# connectors.net
KiCad netlist of a schematic drawn in Altium Designer
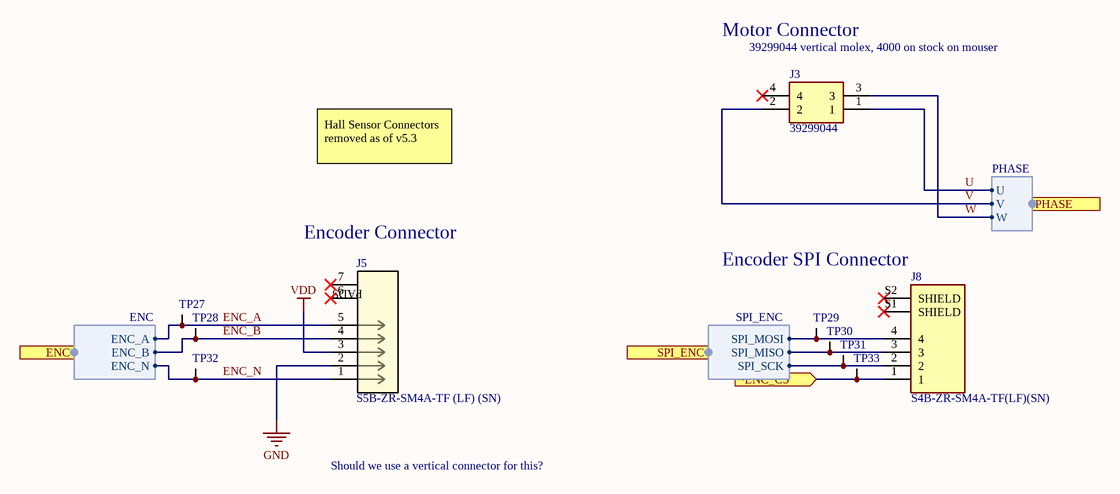
[diagram p0: connectors.SchDoc]

(export (version "E")
  (design (tool "Eeschema 10.0.6"))
  (components
    (comp (ref "J3")
      (value "39299044")
      (footprint "39299044")
      (description "Molex 39299044 4POS Minifit\r\ndual row, vertical")
      (fields (field (name "PART NUMBER") "CN HDR 4POS Molex 39299044 VERT"))
      (libsource (lib "Connector_Library") (part "CN HDR 4POS Molex 39299044 VERT"))
    )
    (comp (ref "J5")
      (value "S5B-ZR-SM4A-TF (LF) (SN)")
      (footprint "JST_S5B-ZR-SM4A-TF")
      (description "Connector Header Surface Mount, Right Angle 5 position 0.059\" (1.50mm)")
      (fields (field (name "PART NUMBER") "CN 5POS JST ZR RA"))
      (libsource (lib "Connector_Library") (part "CN 5POS JST ZR RA"))
    )
    (comp (ref "J8")
      (value "S4B-ZR-SM4A-TF(LF)(SN)")
      (footprint "JST_S4B-ZR-SM4A-TF(LF)(SN)")
      (description "Connector Header Surface Mount, Right Angle 4 position 0.059 (1.50mm)")
      (fields (field (name "MF") "JST Sales") (field (name "PART NUMBER") "CN 4POS JST ZR RA"))
      (libsource (lib "Connector_Library") (part "CN HDR 4POS SMD JST ZR"))
    )
    (comp (ref "TP27")
      (value "ENC_A")
      (footprint "TP")
      (fields (field (name "PART NUMBER") "Test Point (Via)"))
      (libsource (lib "IC_Library") (part "Test Point (Via)"))
    )
    (comp (ref "TP28")
      (value "ENC_B")
      (footprint "TP")
      (fields (field (name "PART NUMBER") "Test Point (Via)"))
      (libsource (lib "IC_Library") (part "Test Point (Via)"))
    )
    (comp (ref "TP29")
      (value "MOSI")
      (footprint "TP")
      (fields (field (name "PART NUMBER") "Test Point (Via)"))
      (libsource (lib "IC_Library") (part "Test Point (Via)"))
    )
    (comp (ref "TP30")
      (value "MISO")
      (footprint "TP")
      (fields (field (name "PART NUMBER") "Test Point (Via)"))
      (libsource (lib "IC_Library") (part "Test Point (Via)"))
    )
    (comp (ref "TP31")
      (value "SCK")
      (footprint "TP")
      (fields (field (name "PART NUMBER") "Test Point (Via)"))
      (libsource (lib "IC_Library") (part "Test Point (Via)"))
    )
    (comp (ref "TP32")
      (value "ENC_N")
      (footprint "TP")
      (fields (field (name "PART NUMBER") "Test Point (Via)"))
      (libsource (lib "IC_Library") (part "Test Point (Via)"))
    )
    (comp (ref "TP33")
      (value "ENC_CS")
      (footprint "TP")
      (fields (field (name "PART NUMBER") "Test Point (Via)"))
      (libsource (lib "IC_Library") (part "Test Point (Via)"))
    )
  )
  (nets
    (net (code "5") (name "/ENC_A") (class "Default")
      (node (ref "J5") (pin "5") (pinfunction "5_5") (pintype "passive"))
      (node (ref "TP27") (pin "1") (pinfunction "1_1") (pintype "passive"))
    )
    (net (code "6") (name "/ENC_B") (class "Default")
      (node (ref "J5") (pin "4") (pinfunction "4_4") (pintype "passive"))
      (node (ref "TP28") (pin "1") (pinfunction "1_1") (pintype "passive"))
    )
    (net (code "7") (name "/ENC_N") (class "Default")
      (node (ref "J5") (pin "1") (pinfunction "1_1") (pintype "passive"))
      (node (ref "TP32") (pin "1") (pinfunction "1_1") (pintype "passive"))
    )
    (net (code "9") (name "/U") (class "Default")
      (node (ref "J3") (pin "1") (pinfunction "1_1") (pintype "passive"))
    )
    (net (code "10") (name "/V") (class "Default")
      (node (ref "J3") (pin "2") (pinfunction "2_2") (pintype "passive"))
    )
    (net (code "11") (name "/W") (class "Default")
      (node (ref "J3") (pin "3") (pinfunction "3_3") (pintype "passive"))
    )
    (net (code "14") (name "/{SPI_ENC}") (class "Default")
      (node (ref "J8") (pin "1") (pinfunction "1_1") (pintype "passive"))
      (node (ref "TP33") (pin "1") (pinfunction "1_1") (pintype "passive"))
    )
    (net (code "15") (name "GND") (class "Default")
      (node (ref "J5") (pin "2") (pinfunction "2_2") (pintype "passive"))
    )
    (net (code "16") (name "Net-(J8-Pad2)") (class "Default")
      (node (ref "J8") (pin "2") (pinfunction "2_2") (pintype "passive"))
      (node (ref "TP31") (pin "1") (pinfunction "1_1") (pintype "passive"))
    )
    (net (code "17") (name "Net-(J8-Pad3)") (class "Default")
      (node (ref "J8") (pin "3") (pinfunction "3_3") (pintype "passive"))
      (node (ref "TP30") (pin "1") (pinfunction "1_1") (pintype "passive"))
    )
    (net (code "18") (name "Net-(J8-Pad4)") (class "Default")
      (node (ref "J8") (pin "4") (pinfunction "4_4") (pintype "passive"))
      (node (ref "TP29") (pin "1") (pinfunction "1_1") (pintype "passive"))
    )
    (net (code "19") (name "VDD") (class "Default")
      (node (ref "J5") (pin "3") (pinfunction "3_3") (pintype "passive"))
    )
    (net (code "20") (name "unconnected-(J3-Pad4)") (class "Default")
      (node (ref "J3") (pin "4") (pinfunction "4_4") (pintype "passive+no_connect"))
    )
    (net (code "21") (name "unconnected-(J5-Pad6)") (class "Default")
      (node (ref "J5") (pin "6") (pinfunction "6_6") (pintype "passive+no_connect"))
    )
    (net (code "22") (name "unconnected-(J5-Pad7)") (class "Default")
      (node (ref "J5") (pin "7") (pinfunction "7_7") (pintype "passive+no_connect"))
    )
    (net (code "23") (name "unconnected-(J8-SHIELD-PadS1)") (class "Default")
      (node (ref "J8") (pin "S1") (pinfunction "SHIELD_S1") (pintype "passive+no_connect"))
    )
    (net (code "24") (name "unconnected-(J8-SHIELD-PadS2)") (class "Default")
      (node (ref "J8") (pin "S2") (pinfunction "SHIELD_S2") (pintype "passive+no_connect"))
    )
  )
)
